# lcd.net
KiCad netlist of a schematic drawn in EAGLE
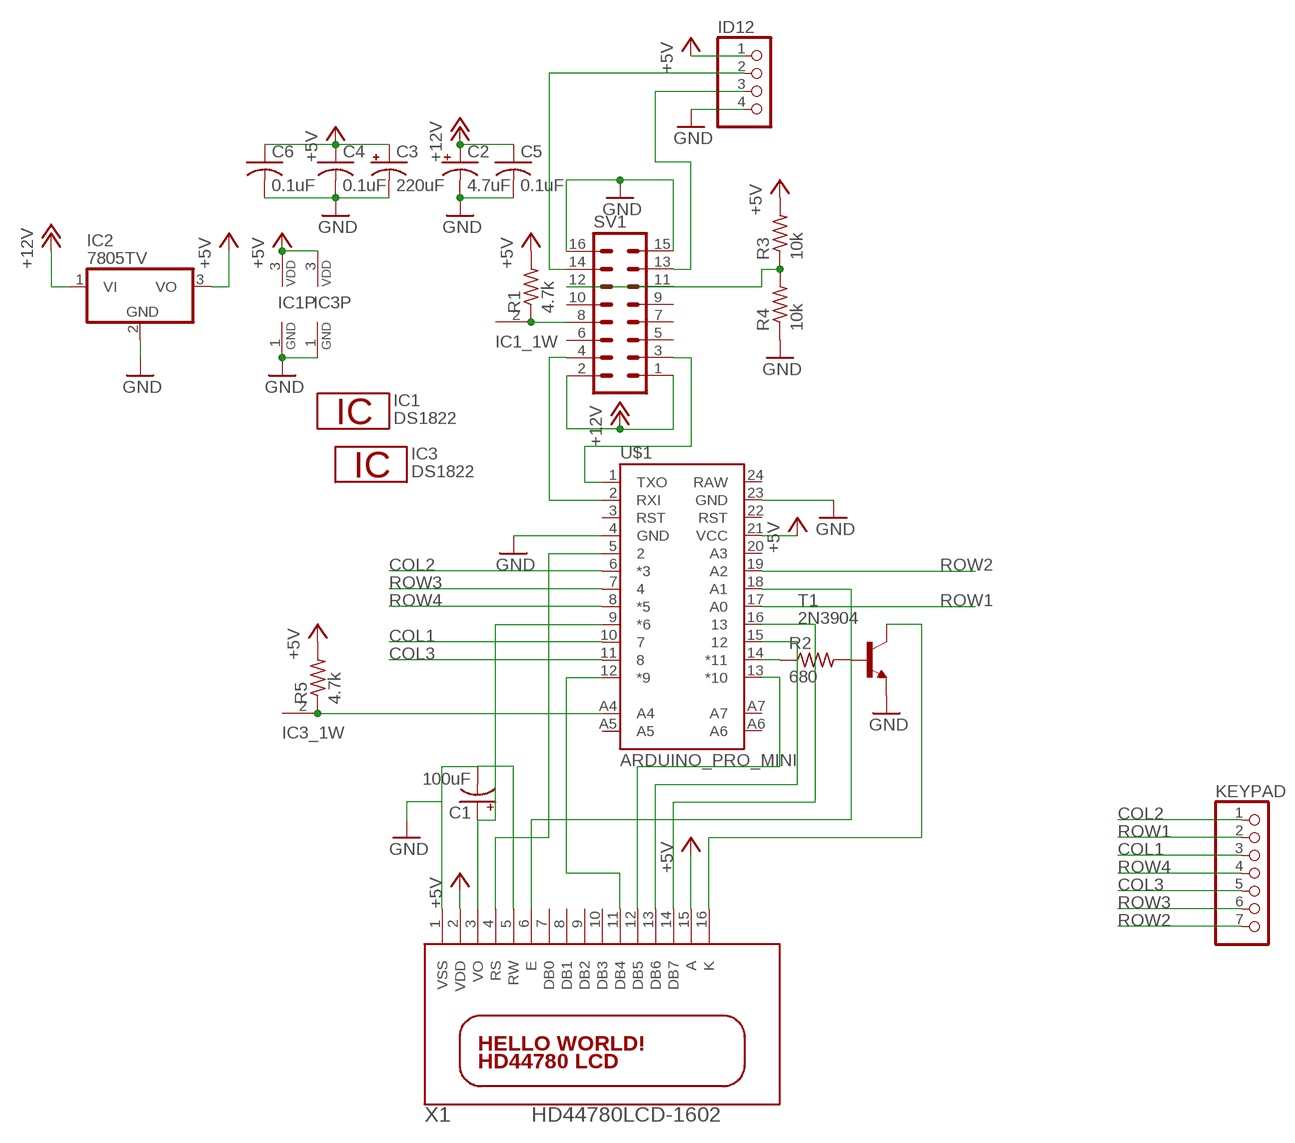
[diagram p0: schematic, sheet 1]

(export (version "E")
  (design (tool "Eeschema 10.0.6"))
  (components
    (comp (ref "C1")
      (value "100uF")
      (footprint "eagle-import:E2,5-7")
      (libsource (lib "eagle-import") (part "CPOL-USE2.5-7"))
    )
    (comp (ref "C2")
      (value "4.7uF")
      (footprint "eagle-import:E2,5-6")
      (libsource (lib "eagle-import") (part "CPOL-USE2.5-6"))
    )
    (comp (ref "C3")
      (value "220uF")
      (footprint "eagle-import:E5-8,5")
      (libsource (lib "eagle-import") (part "CPOL-USE5-8.5"))
    )
    (comp (ref "C4")
      (value "0.1uF")
      (footprint "eagle-import:C025-025X050")
      (libsource (lib "eagle-import") (part "C-US025-025X050"))
    )
    (comp (ref "C5")
      (value "0.1uF")
      (footprint "eagle-import:C025-025X050")
      (libsource (lib "eagle-import") (part "C-US025-025X050"))
    )
    (comp (ref "C6")
      (value "0.1uF")
      (footprint "eagle-import:C025-025X050")
      (libsource (lib "eagle-import") (part "C-US025-025X050"))
    )
    (comp (ref "IC1")
      (value "DS1822")
      (footprint "eagle-import:TO92-")
      (libsource (lib "eagle-import") (part "DS1822"))
    )
    (comp (ref "IC2")
      (value "7805TV")
      (footprint "eagle-import:TO220V")
      (libsource (lib "eagle-import") (part "78TV05"))
    )
    (comp (ref "IC3")
      (value "DS1822")
      (footprint "eagle-import:TO92-")
      (libsource (lib "eagle-import") (part "DS1822"))
    )
    (comp (ref "ID12")
      (value "PINHD-1X4")
      (footprint "eagle-import:1X04")
      (libsource (lib "eagle-import") (part "PINHD-1X4"))
    )
    (comp (ref "KEYPAD")
      (value "PINHD-1X7")
      (footprint "eagle-import:1X07")
      (libsource (lib "eagle-import") (part "PINHD-1X7"))
    )
    (comp (ref "R1")
      (value "4.7k")
      (footprint "eagle-import:0207_5V")
      (libsource (lib "eagle-import") (part "R-US_0207/5V"))
    )
    (comp (ref "R2")
      (value "680")
      (footprint "eagle-import:0207_5V")
      (libsource (lib "eagle-import") (part "R-US_0207/5V"))
    )
    (comp (ref "R3")
      (value "10k")
      (footprint "eagle-import:0204V")
      (libsource (lib "eagle-import") (part "R-US_0204/2V"))
    )
    (comp (ref "R4")
      (value "10k")
      (footprint "eagle-import:0204V")
      (libsource (lib "eagle-import") (part "R-US_0204/2V"))
    )
    (comp (ref "R5")
      (value "4.7k")
      (footprint "eagle-import:0207_5V")
      (libsource (lib "eagle-import") (part "R-US_0207/5V"))
    )
    (comp (ref "SV1")
      (value "ML16")
      (footprint "eagle-import:ML16")
      (libsource (lib "eagle-import") (part "ML16"))
    )
    (comp (ref "T1")
      (value "2N3904")
      (footprint "eagle-import:TO92")
      (libsource (lib "eagle-import") (part "2N3904"))
    )
    (comp (ref "U$1")
      (value "ARDUINO_PRO_MINI")
      (footprint "eagle-import:ARDUINO_PRO_MINI")
      (libsource (lib "eagle-import") (part "ARDUINO_PRO_MINI"))
    )
    (comp (ref "X1")
      (value "HD44780LCD-1602")
      (footprint "eagle-import:LCD1602")
      (libsource (lib "eagle-import") (part "HD44780LCD-1602"))
    )
  )
  (nets
    (net (code "1") (name "+5V") (class "Default")
      (node (ref "C3") (pin "+") (pinfunction "+_+") (pintype "passive"))
      (node (ref "C4") (pin "1") (pinfunction "1_1") (pintype "passive"))
      (node (ref "C6") (pin "1") (pinfunction "1_1") (pintype "passive"))
      (node (ref "IC1") (pin "3") (pinfunction "VDD_3") (pintype "power_in"))
      (node (ref "IC2") (pin "3") (pinfunction "VO_3") (pintype "passive"))
      (node (ref "IC3") (pin "3") (pinfunction "VDD_3") (pintype "power_in"))
      (node (ref "ID12") (pin "1") (pinfunction "1_1") (pintype "passive"))
      (node (ref "R1") (pin "2") (pinfunction "2_2") (pintype "passive"))
      (node (ref "R3") (pin "2") (pinfunction "2_2") (pintype "passive"))
      (node (ref "R5") (pin "2") (pinfunction "2_2") (pintype "passive"))
      (node (ref "U$1") (pin "21") (pinfunction "VCC_21") (pintype "bidirectional"))
      (node (ref "X1") (pin "15") (pinfunction "A_15") (pintype "input"))
      (node (ref "X1") (pin "2") (pinfunction "VDD_2") (pintype "power_in"))
    )
    (net (code "2") (name "+12V") (class "Default")
      (node (ref "C2") (pin "+") (pinfunction "+_+") (pintype "passive"))
      (node (ref "C5") (pin "1") (pinfunction "1_1") (pintype "passive"))
      (node (ref "IC2") (pin "1") (pinfunction "VI_1") (pintype "input"))
      (node (ref "SV1") (pin "1") (pinfunction "1_1") (pintype "passive"))
      (node (ref "SV1") (pin "2") (pinfunction "2_2") (pintype "passive"))
    )
    (net (code "3") (name "/COL1") (class "Default")
      (node (ref "KEYPAD") (pin "3") (pinfunction "3_3") (pintype "passive"))
      (node (ref "U$1") (pin "10") (pinfunction "7_10") (pintype "bidirectional"))
    )
    (net (code "4") (name "/COL2") (class "Default")
      (node (ref "KEYPAD") (pin "1") (pinfunction "1_1") (pintype "passive"))
      (node (ref "U$1") (pin "6") (pinfunction "*3_6") (pintype "bidirectional"))
    )
    (net (code "5") (name "/COL3") (class "Default")
      (node (ref "KEYPAD") (pin "5") (pinfunction "5_5") (pintype "passive"))
      (node (ref "U$1") (pin "11") (pinfunction "8_11") (pintype "bidirectional"))
    )
    (net (code "6") (name "/ROW1") (class "Default")
      (node (ref "KEYPAD") (pin "2") (pinfunction "2_2") (pintype "passive"))
      (node (ref "U$1") (pin "17") (pinfunction "A0_17") (pintype "bidirectional"))
    )
    (net (code "7") (name "/ROW2") (class "Default")
      (node (ref "KEYPAD") (pin "7") (pinfunction "7_7") (pintype "passive"))
      (node (ref "U$1") (pin "19") (pinfunction "A2_19") (pintype "bidirectional"))
    )
    (net (code "8") (name "/ROW3") (class "Default")
      (node (ref "KEYPAD") (pin "6") (pinfunction "6_6") (pintype "passive"))
      (node (ref "U$1") (pin "7") (pinfunction "4_7") (pintype "bidirectional"))
    )
    (net (code "9") (name "/ROW4") (class "Default")
      (node (ref "KEYPAD") (pin "4") (pinfunction "4_4") (pintype "passive"))
      (node (ref "U$1") (pin "8") (pinfunction "*5_8") (pintype "bidirectional"))
    )
    (net (code "10") (name "GND") (class "Default")
      (node (ref "C1") (pin "-") (pinfunction "-_-") (pintype "passive"))
      (node (ref "C2") (pin "-") (pinfunction "-_-") (pintype "passive"))
      (node (ref "C3") (pin "-") (pinfunction "-_-") (pintype "passive"))
      (node (ref "C4") (pin "2") (pinfunction "2_2") (pintype "passive"))
      (node (ref "C5") (pin "2") (pinfunction "2_2") (pintype "passive"))
      (node (ref "C6") (pin "2") (pinfunction "2_2") (pintype "passive"))
      (node (ref "IC1") (pin "1") (pinfunction "GND_1") (pintype "power_in"))
      (node (ref "IC2") (pin "2") (pinfunction "GND_2") (pintype "passive"))
      (node (ref "IC3") (pin "1") (pinfunction "GND_1") (pintype "power_in"))
      (node (ref "ID12") (pin "4") (pinfunction "4_4") (pintype "passive"))
      (node (ref "R4") (pin "1") (pinfunction "1_1") (pintype "passive"))
      (node (ref "SV1") (pin "15") (pinfunction "15_15") (pintype "passive"))
      (node (ref "SV1") (pin "16") (pinfunction "16_16") (pintype "passive"))
      (node (ref "T1") (pin "3") (pinfunction "E_3") (pintype "passive"))
      (node (ref "U$1") (pin "23") (pinfunction "GND_23") (pintype "bidirectional"))
      (node (ref "U$1") (pin "4") (pinfunction "GND_4") (pintype "bidirectional"))
      (node (ref "X1") (pin "1") (pinfunction "VSS_1") (pintype "power_in"))
      (node (ref "X1") (pin "5") (pinfunction "RW_5") (pintype "input"))
    )
    (net (code "11") (name "Net-(IC1C-1W)") (class "Default")
      (node (ref "IC1") (pin "2") (pinfunction "1W_2") (pintype "power_in"))
      (node (ref "R1") (pin "1") (pinfunction "1_1") (pintype "passive"))
      (node (ref "SV1") (pin "8") (pinfunction "8_8") (pintype "passive"))
    )
    (net (code "12") (name "Net-(IC3C-1W)") (class "Default")
      (node (ref "IC3") (pin "2") (pinfunction "1W_2") (pintype "power_in"))
      (node (ref "R5") (pin "1") (pinfunction "1_1") (pintype "passive"))
      (node (ref "U$1") (pin "A4") (pinfunction "A4_A4") (pintype "bidirectional"))
    )
    (net (code "13") (name "Net-(ID12-Pad2)") (class "Default")
      (node (ref "ID12") (pin "2") (pinfunction "2_2") (pintype "passive"))
      (node (ref "SV1") (pin "14") (pinfunction "14_14") (pintype "passive"))
    )
    (net (code "14") (name "Net-(ID12-Pad3)") (class "Default")
      (node (ref "ID12") (pin "3") (pinfunction "3_3") (pintype "passive"))
      (node (ref "SV1") (pin "13") (pinfunction "13_13") (pintype "passive"))
    )
    (net (code "15") (name "Net-(R3-Pad1)") (class "Default")
      (node (ref "R3") (pin "1") (pinfunction "1_1") (pintype "passive"))
      (node (ref "R4") (pin "2") (pinfunction "2_2") (pintype "passive"))
      (node (ref "SV1") (pin "12") (pinfunction "12_12") (pintype "passive"))
    )
    (net (code "16") (name "Net-(T1-B)") (class "Default")
      (node (ref "R2") (pin "2") (pinfunction "2_2") (pintype "passive"))
      (node (ref "T1") (pin "2") (pinfunction "B_2") (pintype "passive"))
    )
    (net (code "17") (name "Net-(T1-C)") (class "Default")
      (node (ref "T1") (pin "1") (pinfunction "C_1") (pintype "passive"))
      (node (ref "X1") (pin "16") (pinfunction "K_16") (pintype "input"))
    )
    (net (code "18") (name "Net-(U$1-*6)") (class "Default")
      (node (ref "C1") (pin "+") (pinfunction "+_+") (pintype "passive"))
      (node (ref "U$1") (pin "9") (pinfunction "*6_9") (pintype "bidirectional"))
      (node (ref "X1") (pin "3") (pinfunction "VO_3") (pintype "input"))
    )
    (net (code "19") (name "Net-(U$1-*9)") (class "Default")
      (node (ref "U$1") (pin "12") (pinfunction "*9_12") (pintype "bidirectional"))
      (node (ref "X1") (pin "11") (pinfunction "DB4_11") (pintype "bidirectional"))
    )
    (net (code "20") (name "Net-(U$1-*10)") (class "Default")
      (node (ref "U$1") (pin "13") (pinfunction "*10_13") (pintype "bidirectional"))
      (node (ref "X1") (pin "12") (pinfunction "DB5_12") (pintype "bidirectional"))
    )
    (net (code "21") (name "Net-(U$1-*11)") (class "Default")
      (node (ref "R2") (pin "1") (pinfunction "1_1") (pintype "passive"))
      (node (ref "U$1") (pin "14") (pinfunction "*11_14") (pintype "bidirectional"))
    )
    (net (code "22") (name "Net-(U$1-2)") (class "Default")
      (node (ref "U$1") (pin "5") (pinfunction "2_5") (pintype "bidirectional"))
      (node (ref "X1") (pin "4") (pinfunction "RS_4") (pintype "input"))
    )
    (net (code "23") (name "Net-(U$1-12)") (class "Default")
      (node (ref "U$1") (pin "15") (pinfunction "12_15") (pintype "bidirectional"))
      (node (ref "X1") (pin "13") (pinfunction "DB6_13") (pintype "bidirectional"))
    )
    (net (code "24") (name "Net-(U$1-13)") (class "Default")
      (node (ref "U$1") (pin "16") (pinfunction "13_16") (pintype "bidirectional"))
      (node (ref "X1") (pin "14") (pinfunction "DB7_14") (pintype "bidirectional"))
    )
    (net (code "25") (name "Net-(U$1-A1)") (class "Default")
      (node (ref "U$1") (pin "18") (pinfunction "A1_18") (pintype "bidirectional"))
      (node (ref "X1") (pin "6") (pinfunction "E_6") (pintype "input"))
    )
    (net (code "26") (name "Net-(U$1-RXI)") (class "Default")
      (node (ref "SV1") (pin "4") (pinfunction "4_4") (pintype "passive"))
      (node (ref "U$1") (pin "2") (pinfunction "RXI_2") (pintype "bidirectional"))
    )
    (net (code "27") (name "Net-(U$1-TXO)") (class "Default")
      (node (ref "SV1") (pin "3") (pinfunction "3_3") (pintype "passive"))
      (node (ref "U$1") (pin "1") (pinfunction "TXO_1") (pintype "bidirectional"))
    )
    (net (code "28") (name "unconnected-(SV1-Pad5)") (class "Default")
      (node (ref "SV1") (pin "5") (pinfunction "5_5") (pintype "passive"))
    )
    (net (code "29") (name "unconnected-(SV1-Pad6)") (class "Default")
      (node (ref "SV1") (pin "6") (pinfunction "6_6") (pintype "passive"))
    )
    (net (code "30") (name "unconnected-(SV1-Pad7)") (class "Default")
      (node (ref "SV1") (pin "7") (pinfunction "7_7") (pintype "passive"))
    )
    (net (code "31") (name "unconnected-(SV1-Pad9)") (class "Default")
      (node (ref "SV1") (pin "9") (pinfunction "9_9") (pintype "passive"))
    )
    (net (code "32") (name "unconnected-(SV1-Pad10)") (class "Default")
      (node (ref "SV1") (pin "10") (pinfunction "10_10") (pintype "passive"))
    )
    (net (code "33") (name "unconnected-(SV1-Pad11)") (class "Default")
      (node (ref "SV1") (pin "11") (pinfunction "11_11") (pintype "passive"))
    )
    (net (code "34") (name "unconnected-(U$1-A3-Pad20)") (class "Default")
      (node (ref "U$1") (pin "20") (pinfunction "A3_20") (pintype "bidirectional"))
    )
    (net (code "35") (name "unconnected-(U$1-PadA5)") (class "Default")
      (node (ref "U$1") (pin "A5") (pinfunction "A5_A5") (pintype "bidirectional"))
    )
    (net (code "36") (name "unconnected-(U$1-PadA6)") (class "Default")
      (node (ref "U$1") (pin "A6") (pinfunction "A6_A6") (pintype "bidirectional"))
    )
    (net (code "37") (name "unconnected-(U$1-PadA7)") (class "Default")
      (node (ref "U$1") (pin "A7") (pinfunction "A7_A7") (pintype "bidirectional"))
    )
    (net (code "38") (name "unconnected-(U$1-RAW-Pad24)") (class "Default")
      (node (ref "U$1") (pin "24") (pinfunction "RAW_24") (pintype "bidirectional"))
    )
    (net (code "39") (name "unconnected-(U$1-RST-Pad3)") (class "Default")
      (node (ref "U$1") (pin "3") (pinfunction "RST_3") (pintype "bidirectional"))
    )
    (net (code "40") (name "unconnected-(U$1-RST-Pad22)") (class "Default")
      (node (ref "U$1") (pin "22") (pinfunction "RST_22") (pintype "bidirectional"))
    )
    (net (code "41") (name "unconnected-(X1-DB0-Pad7)") (class "Default")
      (node (ref "X1") (pin "7") (pinfunction "DB0_7") (pintype "bidirectional"))
    )
    (net (code "42") (name "unconnected-(X1-DB1-Pad8)") (class "Default")
      (node (ref "X1") (pin "8") (pinfunction "DB1_8") (pintype "bidirectional"))
    )
    (net (code "43") (name "unconnected-(X1-DB2-Pad9)") (class "Default")
      (node (ref "X1") (pin "9") (pinfunction "DB2_9") (pintype "bidirectional"))
    )
    (net (code "44") (name "unconnected-(X1-DB3-Pad10)") (class "Default")
      (node (ref "X1") (pin "10") (pinfunction "DB3_10") (pintype "bidirectional"))
    )
  )
)
